# Bus_Control.net
KiCad netlist of a schematic drawn in EAGLE
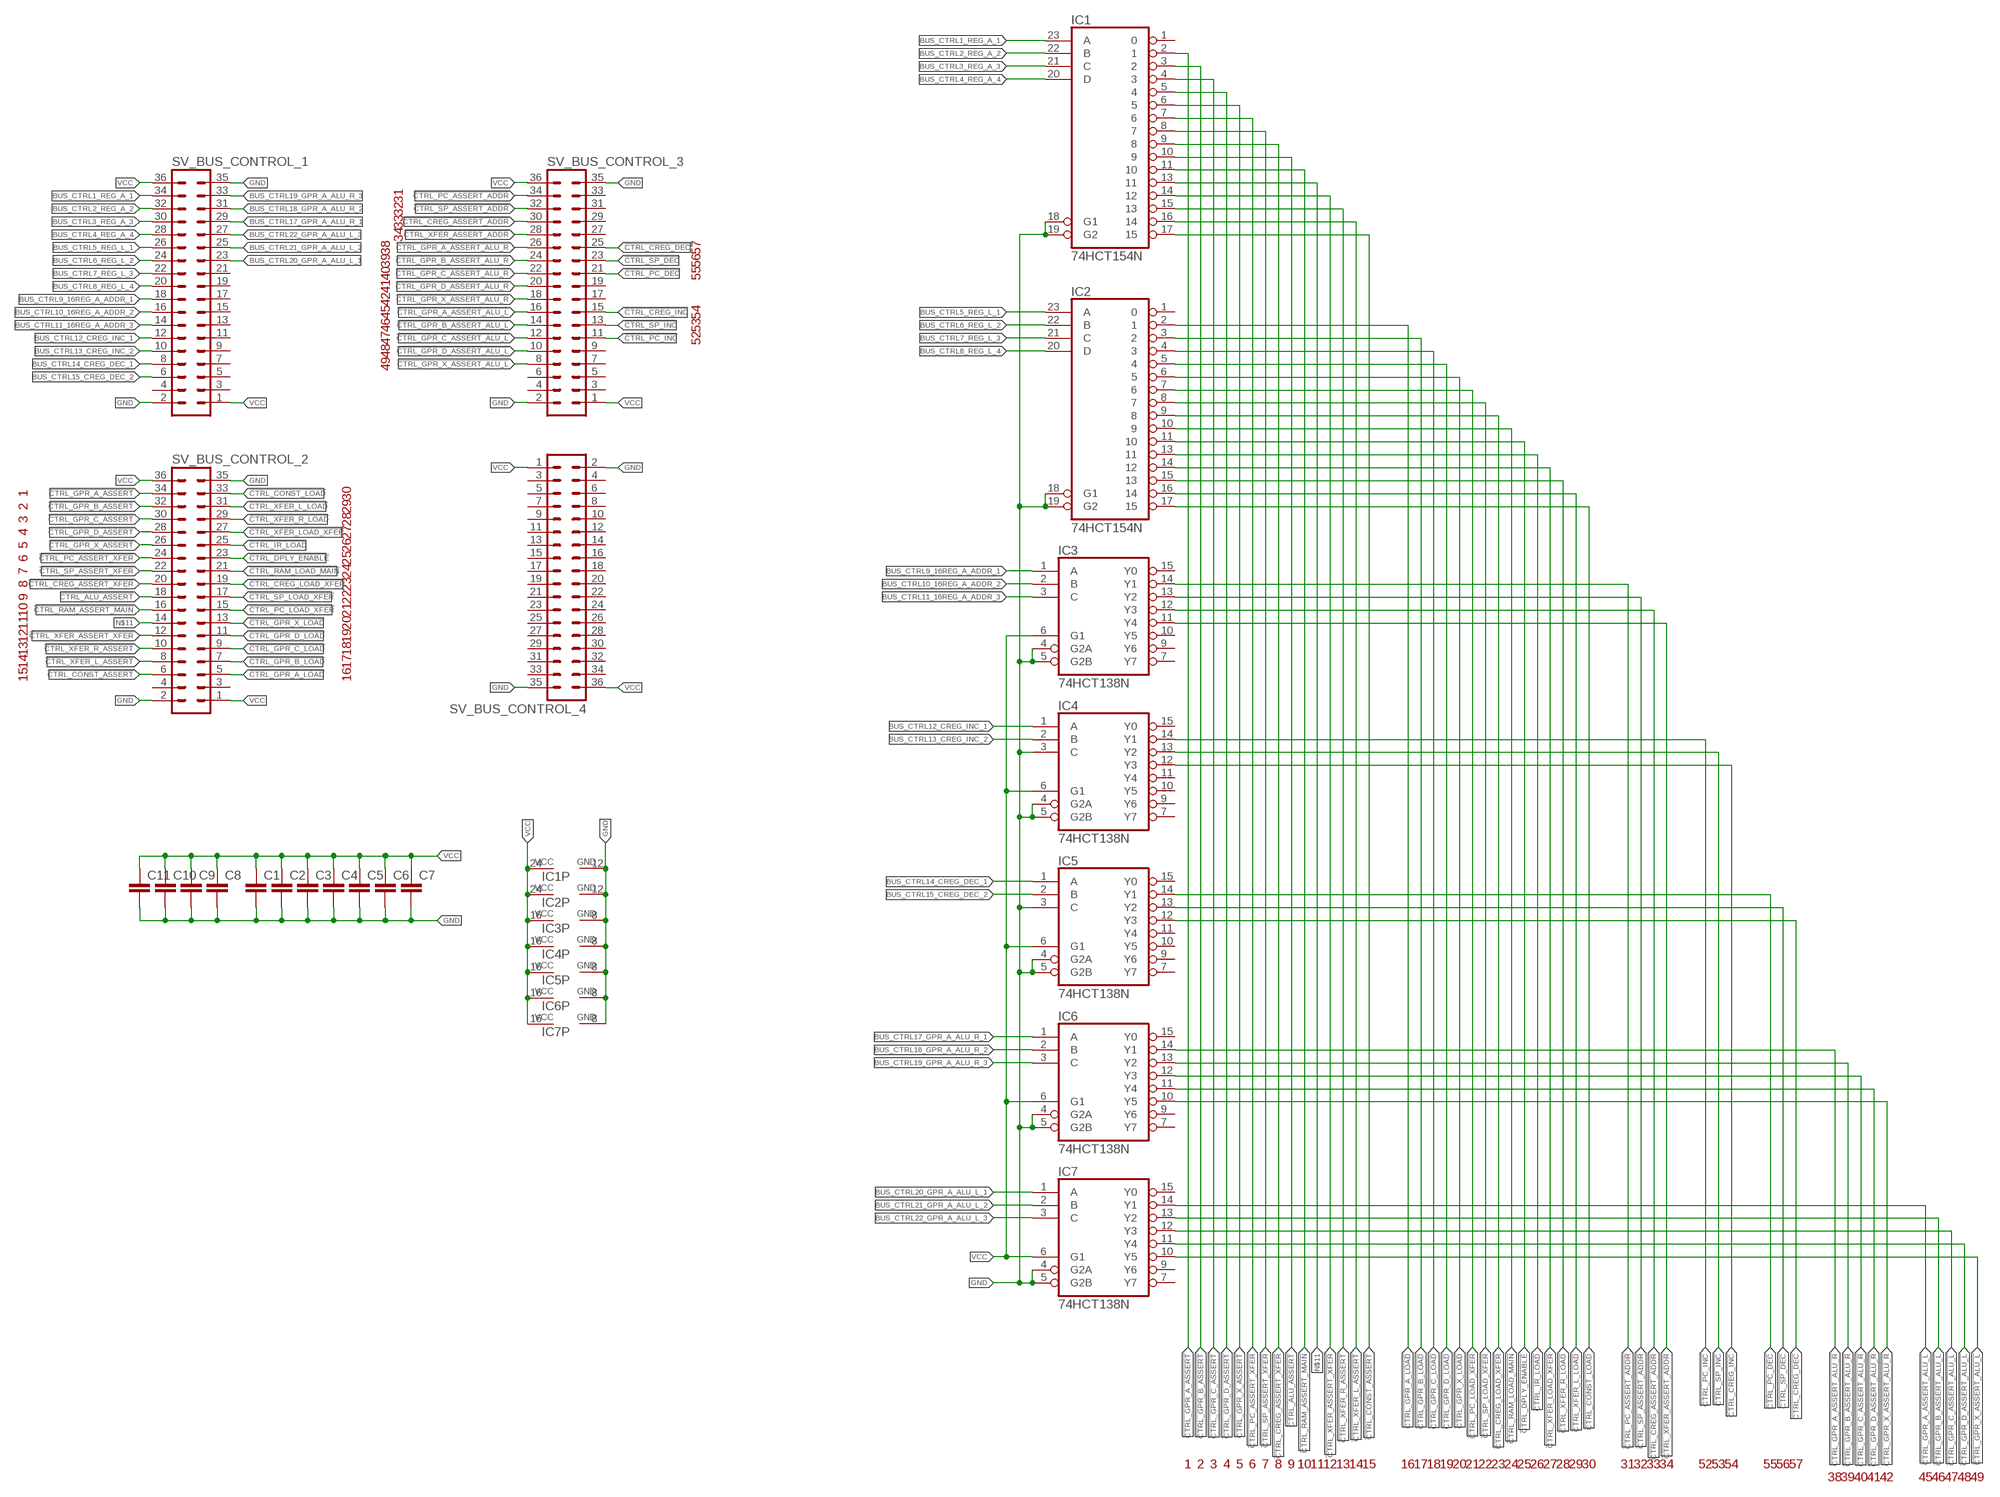
[diagram p0: schematic, sheet 1]

(export (version "E")
  (design (tool "Eeschema 10.0.6"))
  (components
    (comp (ref "C1")
      (value "C-EUC0805")
      (footprint "eagle-import:C0805")
      (libsource (lib "eagle-import") (part "C-EUC0805"))
    )
    (comp (ref "C2")
      (value "C-EUC0805")
      (footprint "eagle-import:C0805")
      (libsource (lib "eagle-import") (part "C-EUC0805"))
    )
    (comp (ref "C3")
      (value "C-EUC0805")
      (footprint "eagle-import:C0805")
      (libsource (lib "eagle-import") (part "C-EUC0805"))
    )
    (comp (ref "C4")
      (value "C-EUC0805")
      (footprint "eagle-import:C0805")
      (libsource (lib "eagle-import") (part "C-EUC0805"))
    )
    (comp (ref "C5")
      (value "C-EUC0805")
      (footprint "eagle-import:C0805")
      (libsource (lib "eagle-import") (part "C-EUC0805"))
    )
    (comp (ref "C6")
      (value "C-EUC0805")
      (footprint "eagle-import:C0805")
      (libsource (lib "eagle-import") (part "C-EUC0805"))
    )
    (comp (ref "C7")
      (value "C-EUC0805")
      (footprint "eagle-import:C0805")
      (libsource (lib "eagle-import") (part "C-EUC0805"))
    )
    (comp (ref "C8")
      (value "C-EUC0805")
      (footprint "eagle-import:C0805")
      (libsource (lib "eagle-import") (part "C-EUC0805"))
    )
    (comp (ref "C9")
      (value "C-EUC0805")
      (footprint "eagle-import:C0805")
      (libsource (lib "eagle-import") (part "C-EUC0805"))
    )
    (comp (ref "C10")
      (value "C-EUC0805")
      (footprint "eagle-import:C0805")
      (libsource (lib "eagle-import") (part "C-EUC0805"))
    )
    (comp (ref "C11")
      (value "C-EUC0805")
      (footprint "eagle-import:C0805")
      (libsource (lib "eagle-import") (part "C-EUC0805"))
    )
    (comp (ref "IC1")
      (value "74HCT154N")
      (footprint "eagle-import:DIL24-6")
      (libsource (lib "eagle-import") (part "74154NHC"))
    )
    (comp (ref "IC2")
      (value "74HCT154N")
      (footprint "eagle-import:DIL24-6")
      (libsource (lib "eagle-import") (part "74154NHC"))
    )
    (comp (ref "IC3")
      (value "74HCT138N")
      (footprint "eagle-import:DIL16")
      (libsource (lib "eagle-import") (part "74138NHCT"))
    )
    (comp (ref "IC4")
      (value "74HCT138N")
      (footprint "eagle-import:DIL16")
      (libsource (lib "eagle-import") (part "74138NHCT"))
    )
    (comp (ref "IC5")
      (value "74HCT138N")
      (footprint "eagle-import:DIL16")
      (libsource (lib "eagle-import") (part "74138NHCT"))
    )
    (comp (ref "IC6")
      (value "74HCT138N")
      (footprint "eagle-import:DIL16")
      (libsource (lib "eagle-import") (part "74138NHCT"))
    )
    (comp (ref "IC7")
      (value "74HCT138N")
      (footprint "eagle-import:DIL16")
      (libsource (lib "eagle-import") (part "74138NHCT"))
    )
    (comp (ref "SV_BUS_CONTROL_1")
      (value "MA18-2")
      (footprint "eagle-import:MA18-2")
      (libsource (lib "eagle-import") (part "MA18-2"))
    )
    (comp (ref "SV_BUS_CONTROL_2")
      (value "MA18-2")
      (footprint "eagle-import:MA18-2")
      (libsource (lib "eagle-import") (part "MA18-2"))
    )
    (comp (ref "SV_BUS_CONTROL_3")
      (value "MA18-2")
      (footprint "eagle-import:MA18-2")
      (libsource (lib "eagle-import") (part "MA18-2"))
    )
    (comp (ref "SV_BUS_CONTROL_4")
      (value "MA18-2")
      (footprint "eagle-import:MA18-2")
      (libsource (lib "eagle-import") (part "MA18-2"))
    )
  )
  (nets
    (net (code "1") (name "/~{CTRL_ALU_ASSERT}") (class "Default")
      (node (ref "IC1") (pin "10") (pinfunction "9_10") (pintype "output"))
      (node (ref "SV_BUS_CONTROL_2") (pin "18") (pinfunction "18_18") (pintype "passive"))
    )
    (net (code "2") (name "/~{CTRL_CONST_ASSERT}") (class "Default")
      (node (ref "IC1") (pin "17") (pinfunction "15_17") (pintype "output"))
      (node (ref "SV_BUS_CONTROL_2") (pin "6") (pinfunction "6_6") (pintype "passive"))
    )
    (net (code "3") (name "/~{CTRL_CONST_LOAD}") (class "Default")
      (node (ref "IC2") (pin "17") (pinfunction "15_17") (pintype "output"))
      (node (ref "SV_BUS_CONTROL_2") (pin "33") (pinfunction "33_33") (pintype "passive"))
    )
    (net (code "4") (name "/~{CTRL_CREG_ASSERT_ADDR}") (class "Default")
      (node (ref "IC3") (pin "12") (pinfunction "Y3_12") (pintype "output"))
      (node (ref "SV_BUS_CONTROL_3") (pin "30") (pinfunction "30_30") (pintype "passive"))
    )
    (net (code "5") (name "/~{CTRL_CREG_ASSERT_XFER}") (class "Default")
      (node (ref "IC1") (pin "9") (pinfunction "8_9") (pintype "output"))
      (node (ref "SV_BUS_CONTROL_2") (pin "20") (pinfunction "20_20") (pintype "passive"))
    )
    (net (code "6") (name "/~{CTRL_CREG_DEC}") (class "Default")
      (node (ref "IC5") (pin "12") (pinfunction "Y3_12") (pintype "output"))
      (node (ref "SV_BUS_CONTROL_3") (pin "25") (pinfunction "25_25") (pintype "passive"))
    )
    (net (code "7") (name "/~{CTRL_CREG_INC}") (class "Default")
      (node (ref "IC4") (pin "12") (pinfunction "Y3_12") (pintype "output"))
      (node (ref "SV_BUS_CONTROL_3") (pin "15") (pinfunction "15_15") (pintype "passive"))
    )
    (net (code "8") (name "/~{CTRL_CREG_LOAD_XFER}") (class "Default")
      (node (ref "IC2") (pin "9") (pinfunction "8_9") (pintype "output"))
      (node (ref "SV_BUS_CONTROL_2") (pin "19") (pinfunction "19_19") (pintype "passive"))
    )
    (net (code "9") (name "/~{CTRL_DPLY_ENABLE}") (class "Default")
      (node (ref "IC2") (pin "11") (pinfunction "10_11") (pintype "output"))
      (node (ref "SV_BUS_CONTROL_2") (pin "23") (pinfunction "23_23") (pintype "passive"))
    )
    (net (code "10") (name "/~{CTRL_GPR_A_ASSERT_ALU_L}") (class "Default")
      (node (ref "IC7") (pin "14") (pinfunction "Y1_14") (pintype "output"))
      (node (ref "SV_BUS_CONTROL_3") (pin "16") (pinfunction "16_16") (pintype "passive"))
    )
    (net (code "11") (name "/~{CTRL_GPR_A_ASSERT_ALU_R}") (class "Default")
      (node (ref "IC6") (pin "14") (pinfunction "Y1_14") (pintype "output"))
      (node (ref "SV_BUS_CONTROL_3") (pin "26") (pinfunction "26_26") (pintype "passive"))
    )
    (net (code "12") (name "/~{CTRL_GPR_A_ASSERT}") (class "Default")
      (node (ref "IC1") (pin "2") (pinfunction "1_2") (pintype "output"))
      (node (ref "SV_BUS_CONTROL_2") (pin "34") (pinfunction "34_34") (pintype "passive"))
    )
    (net (code "13") (name "/~{CTRL_GPR_A_LOAD}") (class "Default")
      (node (ref "IC2") (pin "2") (pinfunction "1_2") (pintype "output"))
      (node (ref "SV_BUS_CONTROL_2") (pin "5") (pinfunction "5_5") (pintype "passive"))
    )
    (net (code "14") (name "/~{CTRL_GPR_B_ASSERT_ALU_L}") (class "Default")
      (node (ref "IC7") (pin "13") (pinfunction "Y2_13") (pintype "output"))
      (node (ref "SV_BUS_CONTROL_3") (pin "14") (pinfunction "14_14") (pintype "passive"))
    )
    (net (code "15") (name "/~{CTRL_GPR_B_ASSERT_ALU_R}") (class "Default")
      (node (ref "IC6") (pin "13") (pinfunction "Y2_13") (pintype "output"))
      (node (ref "SV_BUS_CONTROL_3") (pin "24") (pinfunction "24_24") (pintype "passive"))
    )
    (net (code "16") (name "/~{CTRL_GPR_B_ASSERT}") (class "Default")
      (node (ref "IC1") (pin "3") (pinfunction "2_3") (pintype "output"))
      (node (ref "SV_BUS_CONTROL_2") (pin "32") (pinfunction "32_32") (pintype "passive"))
    )
    (net (code "17") (name "/~{CTRL_GPR_B_LOAD}") (class "Default")
      (node (ref "IC2") (pin "3") (pinfunction "2_3") (pintype "output"))
      (node (ref "SV_BUS_CONTROL_2") (pin "7") (pinfunction "7_7") (pintype "passive"))
    )
    (net (code "18") (name "/~{CTRL_GPR_C_ASSERT_ALU_L}") (class "Default")
      (node (ref "IC7") (pin "12") (pinfunction "Y3_12") (pintype "output"))
      (node (ref "SV_BUS_CONTROL_3") (pin "12") (pinfunction "12_12") (pintype "passive"))
    )
    (net (code "19") (name "/~{CTRL_GPR_C_ASSERT_ALU_R}") (class "Default")
      (node (ref "IC6") (pin "12") (pinfunction "Y3_12") (pintype "output"))
      (node (ref "SV_BUS_CONTROL_3") (pin "22") (pinfunction "22_22") (pintype "passive"))
    )
    (net (code "20") (name "/~{CTRL_GPR_C_ASSERT}") (class "Default")
      (node (ref "IC1") (pin "4") (pinfunction "3_4") (pintype "output"))
      (node (ref "SV_BUS_CONTROL_2") (pin "30") (pinfunction "30_30") (pintype "passive"))
    )
    (net (code "21") (name "/~{CTRL_GPR_C_LOAD}") (class "Default")
      (node (ref "IC2") (pin "4") (pinfunction "3_4") (pintype "output"))
      (node (ref "SV_BUS_CONTROL_2") (pin "9") (pinfunction "9_9") (pintype "passive"))
    )
    (net (code "22") (name "/~{CTRL_GPR_D_ASSERT_ALU_L}") (class "Default")
      (node (ref "IC7") (pin "11") (pinfunction "Y4_11") (pintype "output"))
      (node (ref "SV_BUS_CONTROL_3") (pin "10") (pinfunction "10_10") (pintype "passive"))
    )
    (net (code "23") (name "/~{CTRL_GPR_D_ASSERT_ALU_R}") (class "Default")
      (node (ref "IC6") (pin "11") (pinfunction "Y4_11") (pintype "output"))
      (node (ref "SV_BUS_CONTROL_3") (pin "20") (pinfunction "20_20") (pintype "passive"))
    )
    (net (code "24") (name "/~{CTRL_GPR_D_ASSERT}") (class "Default")
      (node (ref "IC1") (pin "5") (pinfunction "4_5") (pintype "output"))
      (node (ref "SV_BUS_CONTROL_2") (pin "28") (pinfunction "28_28") (pintype "passive"))
    )
    (net (code "25") (name "/~{CTRL_GPR_D_LOAD}") (class "Default")
      (node (ref "IC2") (pin "5") (pinfunction "4_5") (pintype "output"))
      (node (ref "SV_BUS_CONTROL_2") (pin "11") (pinfunction "11_11") (pintype "passive"))
    )
    (net (code "26") (name "/~{CTRL_GPR_X_ASSERT_ALU_L}") (class "Default")
      (node (ref "IC7") (pin "10") (pinfunction "Y5_10") (pintype "output"))
      (node (ref "SV_BUS_CONTROL_3") (pin "8") (pinfunction "8_8") (pintype "passive"))
    )
    (net (code "27") (name "/~{CTRL_GPR_X_ASSERT_ALU_R}") (class "Default")
      (node (ref "IC6") (pin "10") (pinfunction "Y5_10") (pintype "output"))
      (node (ref "SV_BUS_CONTROL_3") (pin "18") (pinfunction "18_18") (pintype "passive"))
    )
    (net (code "28") (name "/~{CTRL_GPR_X_ASSERT}") (class "Default")
      (node (ref "IC1") (pin "6") (pinfunction "5_6") (pintype "output"))
      (node (ref "SV_BUS_CONTROL_2") (pin "26") (pinfunction "26_26") (pintype "passive"))
    )
    (net (code "29") (name "/~{CTRL_GPR_X_LOAD}") (class "Default")
      (node (ref "IC2") (pin "6") (pinfunction "5_6") (pintype "output"))
      (node (ref "SV_BUS_CONTROL_2") (pin "13") (pinfunction "13_13") (pintype "passive"))
    )
    (net (code "30") (name "/~{CTRL_IR_LOAD}") (class "Default")
      (node (ref "IC2") (pin "13") (pinfunction "11_13") (pintype "output"))
      (node (ref "SV_BUS_CONTROL_2") (pin "25") (pinfunction "25_25") (pintype "passive"))
    )
    (net (code "31") (name "/~{CTRL_PC_ASSERT_ADDR}") (class "Default")
      (node (ref "IC3") (pin "14") (pinfunction "Y1_14") (pintype "output"))
      (node (ref "SV_BUS_CONTROL_3") (pin "34") (pinfunction "34_34") (pintype "passive"))
    )
    (net (code "32") (name "/~{CTRL_PC_ASSERT_XFER}") (class "Default")
      (node (ref "IC1") (pin "7") (pinfunction "6_7") (pintype "output"))
      (node (ref "SV_BUS_CONTROL_2") (pin "24") (pinfunction "24_24") (pintype "passive"))
    )
    (net (code "33") (name "/~{CTRL_PC_DEC}") (class "Default")
      (node (ref "IC5") (pin "14") (pinfunction "Y1_14") (pintype "output"))
      (node (ref "SV_BUS_CONTROL_3") (pin "21") (pinfunction "21_21") (pintype "passive"))
    )
    (net (code "34") (name "/~{CTRL_PC_INC}") (class "Default")
      (node (ref "IC4") (pin "14") (pinfunction "Y1_14") (pintype "output"))
      (node (ref "SV_BUS_CONTROL_3") (pin "11") (pinfunction "11_11") (pintype "passive"))
    )
    (net (code "35") (name "/~{CTRL_PC_LOAD_XFER}") (class "Default")
      (node (ref "IC2") (pin "7") (pinfunction "6_7") (pintype "output"))
      (node (ref "SV_BUS_CONTROL_2") (pin "15") (pinfunction "15_15") (pintype "passive"))
    )
    (net (code "36") (name "/~{CTRL_RAM_ASSERT_MAIN}") (class "Default")
      (node (ref "IC1") (pin "11") (pinfunction "10_11") (pintype "output"))
      (node (ref "SV_BUS_CONTROL_2") (pin "16") (pinfunction "16_16") (pintype "passive"))
    )
    (net (code "37") (name "/~{CTRL_RAM_LOAD_MAIN}") (class "Default")
      (node (ref "IC2") (pin "10") (pinfunction "9_10") (pintype "output"))
      (node (ref "SV_BUS_CONTROL_2") (pin "21") (pinfunction "21_21") (pintype "passive"))
    )
    (net (code "38") (name "/~{CTRL_SP_ASSERT_ADDR}") (class "Default")
      (node (ref "IC3") (pin "13") (pinfunction "Y2_13") (pintype "output"))
      (node (ref "SV_BUS_CONTROL_3") (pin "32") (pinfunction "32_32") (pintype "passive"))
    )
    (net (code "39") (name "/~{CTRL_SP_ASSERT_XFER}") (class "Default")
      (node (ref "IC1") (pin "8") (pinfunction "7_8") (pintype "output"))
      (node (ref "SV_BUS_CONTROL_2") (pin "22") (pinfunction "22_22") (pintype "passive"))
    )
    (net (code "40") (name "/~{CTRL_SP_DEC}") (class "Default")
      (node (ref "IC5") (pin "13") (pinfunction "Y2_13") (pintype "output"))
      (node (ref "SV_BUS_CONTROL_3") (pin "23") (pinfunction "23_23") (pintype "passive"))
    )
    (net (code "41") (name "/~{CTRL_SP_INC}") (class "Default")
      (node (ref "IC4") (pin "13") (pinfunction "Y2_13") (pintype "output"))
      (node (ref "SV_BUS_CONTROL_3") (pin "13") (pinfunction "13_13") (pintype "passive"))
    )
    (net (code "42") (name "/~{CTRL_SP_LOAD_XFER}") (class "Default")
      (node (ref "IC2") (pin "8") (pinfunction "7_8") (pintype "output"))
      (node (ref "SV_BUS_CONTROL_2") (pin "17") (pinfunction "17_17") (pintype "passive"))
    )
    (net (code "43") (name "/~{CTRL_XFER_ASSERT_ADDR}") (class "Default")
      (node (ref "IC3") (pin "11") (pinfunction "Y4_11") (pintype "output"))
      (node (ref "SV_BUS_CONTROL_3") (pin "28") (pinfunction "28_28") (pintype "passive"))
    )
    (net (code "44") (name "/~{CTRL_XFER_ASSERT_XFER}") (class "Default")
      (node (ref "IC1") (pin "14") (pinfunction "12_14") (pintype "output"))
      (node (ref "SV_BUS_CONTROL_2") (pin "12") (pinfunction "12_12") (pintype "passive"))
    )
    (net (code "45") (name "/~{CTRL_XFER_LOAD_XFER}") (class "Default")
      (node (ref "IC2") (pin "14") (pinfunction "12_14") (pintype "output"))
      (node (ref "SV_BUS_CONTROL_2") (pin "27") (pinfunction "27_27") (pintype "passive"))
    )
    (net (code "46") (name "/~{CTRL_XFER_L_ASSERT}") (class "Default")
      (node (ref "IC1") (pin "16") (pinfunction "14_16") (pintype "output"))
      (node (ref "SV_BUS_CONTROL_2") (pin "8") (pinfunction "8_8") (pintype "passive"))
    )
    (net (code "47") (name "/~{CTRL_XFER_L_LOAD}") (class "Default")
      (node (ref "IC2") (pin "16") (pinfunction "14_16") (pintype "output"))
      (node (ref "SV_BUS_CONTROL_2") (pin "31") (pinfunction "31_31") (pintype "passive"))
    )
    (net (code "48") (name "/~{CTRL_XFER_R_ASSERT}") (class "Default")
      (node (ref "IC1") (pin "15") (pinfunction "13_15") (pintype "output"))
      (node (ref "SV_BUS_CONTROL_2") (pin "10") (pinfunction "10_10") (pintype "passive"))
    )
    (net (code "49") (name "/~{CTRL_XFER_R_LOAD}") (class "Default")
      (node (ref "IC2") (pin "15") (pinfunction "13_15") (pintype "output"))
      (node (ref "SV_BUS_CONTROL_2") (pin "29") (pinfunction "29_29") (pintype "passive"))
    )
    (net (code "50") (name "BUS_CTRL1_REG_A_1") (class "Default")
      (node (ref "IC1") (pin "23") (pinfunction "A_23") (pintype "input"))
      (node (ref "SV_BUS_CONTROL_1") (pin "34") (pinfunction "34_34") (pintype "passive"))
    )
    (net (code "51") (name "BUS_CTRL2_REG_A_2") (class "Default")
      (node (ref "IC1") (pin "22") (pinfunction "B_22") (pintype "input"))
      (node (ref "SV_BUS_CONTROL_1") (pin "32") (pinfunction "32_32") (pintype "passive"))
    )
    (net (code "52") (name "BUS_CTRL3_REG_A_3") (class "Default")
      (node (ref "IC1") (pin "21") (pinfunction "C_21") (pintype "input"))
      (node (ref "SV_BUS_CONTROL_1") (pin "30") (pinfunction "30_30") (pintype "passive"))
    )
    (net (code "53") (name "BUS_CTRL4_REG_A_4") (class "Default")
      (node (ref "IC1") (pin "20") (pinfunction "D_20") (pintype "input"))
      (node (ref "SV_BUS_CONTROL_1") (pin "28") (pinfunction "28_28") (pintype "passive"))
    )
    (net (code "54") (name "BUS_CTRL5_REG_L_1") (class "Default")
      (node (ref "IC2") (pin "23") (pinfunction "A_23") (pintype "input"))
      (node (ref "SV_BUS_CONTROL_1") (pin "26") (pinfunction "26_26") (pintype "passive"))
    )
    (net (code "55") (name "BUS_CTRL6_REG_L_2") (class "Default")
      (node (ref "IC2") (pin "22") (pinfunction "B_22") (pintype "input"))
      (node (ref "SV_BUS_CONTROL_1") (pin "24") (pinfunction "24_24") (pintype "passive"))
    )
    (net (code "56") (name "BUS_CTRL7_REG_L_3") (class "Default")
      (node (ref "IC2") (pin "21") (pinfunction "C_21") (pintype "input"))
      (node (ref "SV_BUS_CONTROL_1") (pin "22") (pinfunction "22_22") (pintype "passive"))
    )
    (net (code "57") (name "BUS_CTRL8_REG_L_4") (class "Default")
      (node (ref "IC2") (pin "20") (pinfunction "D_20") (pintype "input"))
      (node (ref "SV_BUS_CONTROL_1") (pin "20") (pinfunction "20_20") (pintype "passive"))
    )
    (net (code "58") (name "BUS_CTRL9_16REG_A_ADDR_1") (class "Default")
      (node (ref "IC3") (pin "1") (pinfunction "A_1") (pintype "input"))
      (node (ref "SV_BUS_CONTROL_1") (pin "18") (pinfunction "18_18") (pintype "passive"))
    )
    (net (code "59") (name "BUS_CTRL10_16REG_A_ADDR_2") (class "Default")
      (node (ref "IC3") (pin "2") (pinfunction "B_2") (pintype "input"))
      (node (ref "SV_BUS_CONTROL_1") (pin "16") (pinfunction "16_16") (pintype "passive"))
    )
    (net (code "60") (name "BUS_CTRL11_16REG_A_ADDR_3") (class "Default")
      (node (ref "IC3") (pin "3") (pinfunction "C_3") (pintype "input"))
      (node (ref "SV_BUS_CONTROL_1") (pin "14") (pinfunction "14_14") (pintype "passive"))
    )
    (net (code "61") (name "BUS_CTRL12_CREG_INC_1") (class "Default")
      (node (ref "IC4") (pin "1") (pinfunction "A_1") (pintype "input"))
      (node (ref "SV_BUS_CONTROL_1") (pin "12") (pinfunction "12_12") (pintype "passive"))
    )
    (net (code "62") (name "BUS_CTRL13_CREG_INC_2") (class "Default")
      (node (ref "IC4") (pin "2") (pinfunction "B_2") (pintype "input"))
      (node (ref "SV_BUS_CONTROL_1") (pin "10") (pinfunction "10_10") (pintype "passive"))
    )
    (net (code "63") (name "BUS_CTRL14_CREG_DEC_1") (class "Default")
      (node (ref "IC5") (pin "1") (pinfunction "A_1") (pintype "input"))
      (node (ref "SV_BUS_CONTROL_1") (pin "8") (pinfunction "8_8") (pintype "passive"))
    )
    (net (code "64") (name "BUS_CTRL15_CREG_DEC_2") (class "Default")
      (node (ref "IC5") (pin "2") (pinfunction "B_2") (pintype "input"))
      (node (ref "SV_BUS_CONTROL_1") (pin "6") (pinfunction "6_6") (pintype "passive"))
    )
    (net (code "65") (name "BUS_CTRL17_GPR_A_ALU_R_1") (class "Default")
      (node (ref "IC6") (pin "1") (pinfunction "A_1") (pintype "input"))
      (node (ref "SV_BUS_CONTROL_1") (pin "29") (pinfunction "29_29") (pintype "passive"))
    )
    (net (code "66") (name "BUS_CTRL18_GPR_A_ALU_R_2") (class "Default")
      (node (ref "IC6") (pin "2") (pinfunction "B_2") (pintype "input"))
      (node (ref "SV_BUS_CONTROL_1") (pin "31") (pinfunction "31_31") (pintype "passive"))
    )
    (net (code "67") (name "BUS_CTRL19_GPR_A_ALU_R_3") (class "Default")
      (node (ref "IC6") (pin "3") (pinfunction "C_3") (pintype "input"))
      (node (ref "SV_BUS_CONTROL_1") (pin "33") (pinfunction "33_33") (pintype "passive"))
    )
    (net (code "68") (name "BUS_CTRL20_GPR_A_ALU_L_1") (class "Default")
      (node (ref "IC7") (pin "1") (pinfunction "A_1") (pintype "input"))
      (node (ref "SV_BUS_CONTROL_1") (pin "23") (pinfunction "23_23") (pintype "passive"))
    )
    (net (code "69") (name "BUS_CTRL21_GPR_A_ALU_L_2") (class "Default")
      (node (ref "IC7") (pin "2") (pinfunction "B_2") (pintype "input"))
      (node (ref "SV_BUS_CONTROL_1") (pin "25") (pinfunction "25_25") (pintype "passive"))
    )
    (net (code "70") (name "BUS_CTRL22_GPR_A_ALU_L_3") (class "Default")
      (node (ref "IC7") (pin "3") (pinfunction "C_3") (pintype "input"))
      (node (ref "SV_BUS_CONTROL_1") (pin "27") (pinfunction "27_27") (pintype "passive"))
    )
    (net (code "71") (name "GND") (class "Default")
      (node (ref "C1") (pin "2") (pinfunction "2_2") (pintype "passive"))
      (node (ref "C10") (pin "2") (pinfunction "2_2") (pintype "passive"))
      (node (ref "C11") (pin "2") (pinfunction "2_2") (pintype "passive"))
      (node (ref "C2") (pin "2") (pinfunction "2_2") (pintype "passive"))
      (node (ref "C3") (pin "2") (pinfunction "2_2") (pintype "passive"))
      (node (ref "C4") (pin "2") (pinfunction "2_2") (pintype "passive"))
      (node (ref "C5") (pin "2") (pinfunction "2_2") (pintype "passive"))
      (node (ref "C6") (pin "2") (pinfunction "2_2") (pintype "passive"))
      (node (ref "C7") (pin "2") (pinfunction "2_2") (pintype "passive"))
      (node (ref "C8") (pin "2") (pinfunction "2_2") (pintype "passive"))
      (node (ref "C9") (pin "2") (pinfunction "2_2") (pintype "passive"))
      (node (ref "IC1") (pin "12") (pinfunction "GND_12") (pintype "power_in"))
      (node (ref "IC1") (pin "18") (pinfunction "G1_18") (pintype "input"))
      (node (ref "IC1") (pin "19") (pinfunction "G2_19") (pintype "input"))
      (node (ref "IC2") (pin "12") (pinfunction "GND_12") (pintype "power_in"))
      (node (ref "IC2") (pin "18") (pinfunction "G1_18") (pintype "input"))
      (node (ref "IC2") (pin "19") (pinfunction "G2_19") (pintype "input"))
      (node (ref "IC3") (pin "4") (pinfunction "G2A_4") (pintype "input"))
      (node (ref "IC3") (pin "5") (pinfunction "G2B_5") (pintype "input"))
      (node (ref "IC3") (pin "8") (pinfunction "GND_8") (pintype "power_in"))
      (node (ref "IC4") (pin "3") (pinfunction "C_3") (pintype "input"))
      (node (ref "IC4") (pin "4") (pinfunction "G2A_4") (pintype "input"))
      (node (ref "IC4") (pin "5") (pinfunction "G2B_5") (pintype "input"))
      (node (ref "IC4") (pin "8") (pinfunction "GND_8") (pintype "power_in"))
      (node (ref "IC5") (pin "3") (pinfunction "C_3") (pintype "input"))
      (node (ref "IC5") (pin "4") (pinfunction "G2A_4") (pintype "input"))
      (node (ref "IC5") (pin "5") (pinfunction "G2B_5") (pintype "input"))
      (node (ref "IC5") (pin "8") (pinfunction "GND_8") (pintype "power_in"))
      (node (ref "IC6") (pin "4") (pinfunction "G2A_4") (pintype "input"))
      (node (ref "IC6") (pin "5") (pinfunction "G2B_5") (pintype "input"))
      (node (ref "IC6") (pin "8") (pinfunction "GND_8") (pintype "power_in"))
      (node (ref "IC7") (pin "4") (pinfunction "G2A_4") (pintype "input"))
      (node (ref "IC7") (pin "5") (pinfunction "G2B_5") (pintype "input"))
      (node (ref "IC7") (pin "8") (pinfunction "GND_8") (pintype "power_in"))
      (node (ref "SV_BUS_CONTROL_1") (pin "2") (pinfunction "2_2") (pintype "passive"))
      (node (ref "SV_BUS_CONTROL_1") (pin "35") (pinfunction "35_35") (pintype "passive"))
      (node (ref "SV_BUS_CONTROL_2") (pin "2") (pinfunction "2_2") (pintype "passive"))
      (node (ref "SV_BUS_CONTROL_2") (pin "35") (pinfunction "35_35") (pintype "passive"))
      (node (ref "SV_BUS_CONTROL_3") (pin "2") (pinfunction "2_2") (pintype "passive"))
      (node (ref "SV_BUS_CONTROL_3") (pin "35") (pinfunction "35_35") (pintype "passive"))
      (node (ref "SV_BUS_CONTROL_4") (pin "2") (pinfunction "2_2") (pintype "passive"))
      (node (ref "SV_BUS_CONTROL_4") (pin "35") (pinfunction "35_35") (pintype "passive"))
    )
    (net (code "72") (name "N$11") (class "Default")
      (node (ref "IC1") (pin "13") (pinfunction "11_13") (pintype "output"))
      (node (ref "SV_BUS_CONTROL_2") (pin "14") (pinfunction "14_14") (pintype "passive"))
    )
    (net (code "73") (name "VCC") (class "Default")
      (node (ref "C1") (pin "1") (pinfunction "1_1") (pintype "passive"))
      (node (ref "C10") (pin "1") (pinfunction "1_1") (pintype "passive"))
      (node (ref "C11") (pin "1") (pinfunction "1_1") (pintype "passive"))
      (node (ref "C2") (pin "1") (pinfunction "1_1") (pintype "passive"))
      (node (ref "C3") (pin "1") (pinfunction "1_1") (pintype "passive"))
      (node (ref "C4") (pin "1") (pinfunction "1_1") (pintype "passive"))
      (node (ref "C5") (pin "1") (pinfunction "1_1") (pintype "passive"))
      (node (ref "C6") (pin "1") (pinfunction "1_1") (pintype "passive"))
      (node (ref "C7") (pin "1") (pinfunction "1_1") (pintype "passive"))
      (node (ref "C8") (pin "1") (pinfunction "1_1") (pintype "passive"))
      (node (ref "C9") (pin "1") (pinfunction "1_1") (pintype "passive"))
      (node (ref "IC1") (pin "24") (pinfunction "VCC_24") (pintype "power_in"))
      (node (ref "IC2") (pin "24") (pinfunction "VCC_24") (pintype "power_in"))
      (node (ref "IC3") (pin "16") (pinfunction "VCC_16") (pintype "power_in"))
      (node (ref "IC3") (pin "6") (pinfunction "G1_6") (pintype "input"))
      (node (ref "IC4") (pin "16") (pinfunction "VCC_16") (pintype "power_in"))
      (node (ref "IC4") (pin "6") (pinfunction "G1_6") (pintype "input"))
      (node (ref "IC5") (pin "16") (pinfunction "VCC_16") (pintype "power_in"))
      (node (ref "IC5") (pin "6") (pinfunction "G1_6") (pintype "input"))
      (node (ref "IC6") (pin "16") (pinfunction "VCC_16") (pintype "power_in"))
      (node (ref "IC6") (pin "6") (pinfunction "G1_6") (pintype "input"))
      (node (ref "IC7") (pin "16") (pinfunction "VCC_16") (pintype "power_in"))
      (node (ref "IC7") (pin "6") (pinfunction "G1_6") (pintype "input"))
      (node (ref "SV_BUS_CONTROL_1") (pin "1") (pinfunction "1_1") (pintype "passive"))
      (node (ref "SV_BUS_CONTROL_1") (pin "36") (pinfunction "36_36") (pintype "passive"))
      (node (ref "SV_BUS_CONTROL_2") (pin "1") (pinfunction "1_1") (pintype "passive"))
      (node (ref "SV_BUS_CONTROL_2") (pin "36") (pinfunction "36_36") (pintype "passive"))
      (node (ref "SV_BUS_CONTROL_3") (pin "1") (pinfunction "1_1") (pintype "passive"))
      (node (ref "SV_BUS_CONTROL_3") (pin "36") (pinfunction "36_36") (pintype "passive"))
      (node (ref "SV_BUS_CONTROL_4") (pin "1") (pinfunction "1_1") (pintype "passive"))
      (node (ref "SV_BUS_CONTROL_4") (pin "36") (pinfunction "36_36") (pintype "passive"))
    )
    (net (code "74") (name "unconnected-(IC1A-0-Pad1)") (class "Default")
      (node (ref "IC1") (pin "1") (pinfunction "0_1") (pintype "output"))
    )
    (net (code "75") (name "unconnected-(IC2A-0-Pad1)") (class "Default")
      (node (ref "IC2") (pin "1") (pinfunction "0_1") (pintype "output"))
    )
    (net (code "76") (name "unconnected-(IC3A-Y0-Pad15)") (class "Default")
      (node (ref "IC3") (pin "15") (pinfunction "Y0_15") (pintype "output"))
    )
    (net (code "77") (name "unconnected-(IC3A-Y5-Pad10)") (class "Default")
      (node (ref "IC3") (pin "10") (pinfunction "Y5_10") (pintype "output"))
    )
    (net (code "78") (name "unconnected-(IC3A-Y6-Pad9)") (class "Default")
      (node (ref "IC3") (pin "9") (pinfunction "Y6_9") (pintype "output"))
    )
    (net (code "79") (name "unconnected-(IC3A-Y7-Pad7)") (class "Default")
      (node (ref "IC3") (pin "7") (pinfunction "Y7_7") (pintype "output"))
    )
    (net (code "80") (name "unconnected-(IC4A-Y0-Pad15)") (class "Default")
      (node (ref "IC4") (pin "15") (pinfunction "Y0_15") (pintype "output"))
    )
    (net (code "81") (name "unconnected-(IC4A-Y4-Pad11)") (class "Default")
      (node (ref "IC4") (pin "11") (pinfunction "Y4_11") (pintype "output"))
    )
    (net (code "82") (name "unconnected-(IC4A-Y5-Pad10)") (class "Default")
      (node (ref "IC4") (pin "10") (pinfunction "Y5_10") (pintype "output"))
    )
    (net (code "83") (name "unconnected-(IC4A-Y6-Pad9)") (class "Default")
      (node (ref "IC4") (pin "9") (pinfunction "Y6_9") (pintype "output"))
    )
    (net (code "84") (name "unconnected-(IC4A-Y7-Pad7)") (class "Default")
      (node (ref "IC4") (pin "7") (pinfunction "Y7_7") (pintype "output"))
    )
    (net (code "85") (name "unconnected-(IC5A-Y0-Pad15)") (class "Default")
      (node (ref "IC5") (pin "15") (pinfunction "Y0_15") (pintype "output"))
    )
    (net (code "86") (name "unconnected-(IC5A-Y4-Pad11)") (class "Default")
      (node (ref "IC5") (pin "11") (pinfunction "Y4_11") (pintype "output"))
    )
    (net (code "87") (name "unconnected-(IC5A-Y5-Pad10)") (class "Default")
      (node (ref "IC5") (pin "10") (pinfunction "Y5_10") (pintype "output"))
    )
    (net (code "88") (name "unconnected-(IC5A-Y6-Pad9)") (class "Default")
      (node (ref "IC5") (pin "9") (pinfunction "Y6_9") (pintype "output"))
    )
    (net (code "89") (name "unconnected-(IC5A-Y7-Pad7)") (class "Default")
      (node (ref "IC5") (pin "7") (pinfunction "Y7_7") (pintype "output"))
    )
    (net (code "90") (name "unconnected-(IC6A-Y0-Pad15)") (class "Default")
      (node (ref "IC6") (pin "15") (pinfunction "Y0_15") (pintype "output"))
    )
    (net (code "91") (name "unconnected-(IC6A-Y6-Pad9)") (class "Default")
      (node (ref "IC6") (pin "9") (pinfunction "Y6_9") (pintype "output"))
    )
    (net (code "92") (name "unconnected-(IC6A-Y7-Pad7)") (class "Default")
      (node (ref "IC6") (pin "7") (pinfunction "Y7_7") (pintype "output"))
    )
    (net (code "93") (name "unconnected-(IC7A-Y0-Pad15)") (class "Default")
      (node (ref "IC7") (pin "15") (pinfunction "Y0_15") (pintype "output"))
    )
    (net (code "94") (name "unconnected-(IC7A-Y6-Pad9)") (class "Default")
      (node (ref "IC7") (pin "9") (pinfunction "Y6_9") (pintype "output"))
    )
    (net (code "95") (name "unconnected-(IC7A-Y7-Pad7)") (class "Default")
      (node (ref "IC7") (pin "7") (pinfunction "Y7_7") (pintype "output"))
    )
    (net (code "96") (name "unconnected-(SV_BUS_CONTROL_1-Pad3)") (class "Default")
      (node (ref "SV_BUS_CONTROL_1") (pin "3") (pinfunction "3_3") (pintype "passive"))
    )
    (net (code "97") (name "unconnected-(SV_BUS_CONTROL_1-Pad4)") (class "Default")
      (node (ref "SV_BUS_CONTROL_1") (pin "4") (pinfunction "4_4") (pintype "passive"))
    )
    (net (code "98") (name "unconnected-(SV_BUS_CONTROL_1-Pad5)") (class "Default")
      (node (ref "SV_BUS_CONTROL_1") (pin "5") (pinfunction "5_5") (pintype "passive"))
    )
    (net (code "99") (name "unconnected-(SV_BUS_CONTROL_1-Pad7)") (class "Default")
      (node (ref "SV_BUS_CONTROL_1") (pin "7") (pinfunction "7_7") (pintype "passive"))
    )
    (net (code "100") (name "unconnected-(SV_BUS_CONTROL_1-Pad9)") (class "Default")
      (node (ref "SV_BUS_CONTROL_1") (pin "9") (pinfunction "9_9") (pintype "passive"))
    )
    (net (code "101") (name "unconnected-(SV_BUS_CONTROL_1-Pad11)") (class "Default")
      (node (ref "SV_BUS_CONTROL_1") (pin "11") (pinfunction "11_11") (pintype "passive"))
    )
    (net (code "102") (name "unconnected-(SV_BUS_CONTROL_1-Pad13)") (class "Default")
      (node (ref "SV_BUS_CONTROL_1") (pin "13") (pinfunction "13_13") (pintype "passive"))
    )
    (net (code "103") (name "unconnected-(SV_BUS_CONTROL_1-Pad15)") (class "Default")
      (node (ref "SV_BUS_CONTROL_1") (pin "15") (pinfunction "15_15") (pintype "passive"))
    )
    (net (code "104") (name "unconnected-(SV_BUS_CONTROL_1-Pad17)") (class "Default")
      (node (ref "SV_BUS_CONTROL_1") (pin "17") (pinfunction "17_17") (pintype "passive"))
    )
    (net (code "105") (name "unconnected-(SV_BUS_CONTROL_1-Pad19)") (class "Default")
      (node (ref "SV_BUS_CONTROL_1") (pin "19") (pinfunction "19_19") (pintype "passive"))
    )
    (net (code "106") (name "unconnected-(SV_BUS_CONTROL_1-Pad21)") (class "Default")
      (node (ref "SV_BUS_CONTROL_1") (pin "21") (pinfunction "21_21") (pintype "passive"))
    )
    (net (code "107") (name "unconnected-(SV_BUS_CONTROL_2-Pad3)") (class "Default")
      (node (ref "SV_BUS_CONTROL_2") (pin "3") (pinfunction "3_3") (pintype "passive"))
    )
    (net (code "108") (name "unconnected-(SV_BUS_CONTROL_2-Pad4)") (class "Default")
      (node (ref "SV_BUS_CONTROL_2") (pin "4") (pinfunction "4_4") (pintype "passive"))
    )
    (net (code "109") (name "unconnected-(SV_BUS_CONTROL_3-Pad3)") (class "Default")
      (node (ref "SV_BUS_CONTROL_3") (pin "3") (pinfunction "3_3") (pintype "passive"))
    )
    (net (code "110") (name "unconnected-(SV_BUS_CONTROL_3-Pad4)") (class "Default")
      (node (ref "SV_BUS_CONTROL_3") (pin "4") (pinfunction "4_4") (pintype "passive"))
    )
    (net (code "111") (name "unconnected-(SV_BUS_CONTROL_3-Pad5)") (class "Default")
      (node (ref "SV_BUS_CONTROL_3") (pin "5") (pinfunction "5_5") (pintype "passive"))
    )
    (net (code "112") (name "unconnected-(SV_BUS_CONTROL_3-Pad6)") (class "Default")
      (node (ref "SV_BUS_CONTROL_3") (pin "6") (pinfunction "6_6") (pintype "passive"))
    )
    (net (code "113") (name "unconnected-(SV_BUS_CONTROL_3-Pad7)") (class "Default")
      (node (ref "SV_BUS_CONTROL_3") (pin "7") (pinfunction "7_7") (pintype "passive"))
    )
    (net (code "114") (name "unconnected-(SV_BUS_CONTROL_3-Pad9)") (class "Default")
      (node (ref "SV_BUS_CONTROL_3") (pin "9") (pinfunction "9_9") (pintype "passive"))
    )
    (net (code "115") (name "unconnected-(SV_BUS_CONTROL_3-Pad17)") (class "Default")
      (node (ref "SV_BUS_CONTROL_3") (pin "17") (pinfunction "17_17") (pintype "passive"))
    )
    (net (code "116") (name "unconnected-(SV_BUS_CONTROL_3-Pad19)") (class "Default")
      (node (ref "SV_BUS_CONTROL_3") (pin "19") (pinfunction "19_19") (pintype "passive"))
    )
    (net (code "117") (name "unconnected-(SV_BUS_CONTROL_3-Pad27)") (class "Default")
      (node (ref "SV_BUS_CONTROL_3") (pin "27") (pinfunction "27_27") (pintype "passive"))
    )
    (net (code "118") (name "unconnected-(SV_BUS_CONTROL_3-Pad29)") (class "Default")
      (node (ref "SV_BUS_CONTROL_3") (pin "29") (pinfunction "29_29") (pintype "passive"))
    )
    (net (code "119") (name "unconnected-(SV_BUS_CONTROL_3-Pad31)") (class "Default")
      (node (ref "SV_BUS_CONTROL_3") (pin "31") (pinfunction "31_31") (pintype "passive"))
    )
    (net (code "120") (name "unconnected-(SV_BUS_CONTROL_3-Pad33)") (class "Default")
      (node (ref "SV_BUS_CONTROL_3") (pin "33") (pinfunction "33_33") (pintype "passive"))
    )
    (net (code "121") (name "unconnected-(SV_BUS_CONTROL_4-Pad3)") (class "Default")
      (node (ref "SV_BUS_CONTROL_4") (pin "3") (pinfunction "3_3") (pintype "passive"))
    )
    (net (code "122") (name "unconnected-(SV_BUS_CONTROL_4-Pad4)") (class "Default")
      (node (ref "SV_BUS_CONTROL_4") (pin "4") (pinfunction "4_4") (pintype "passive"))
    )
    (net (code "123") (name "unconnected-(SV_BUS_CONTROL_4-Pad5)") (class "Default")
      (node (ref "SV_BUS_CONTROL_4") (pin "5") (pinfunction "5_5") (pintype "passive"))
    )
    (net (code "124") (name "unconnected-(SV_BUS_CONTROL_4-Pad6)") (class "Default")
      (node (ref "SV_BUS_CONTROL_4") (pin "6") (pinfunction "6_6") (pintype "passive"))
    )
    (net (code "125") (name "unconnected-(SV_BUS_CONTROL_4-Pad7)") (class "Default")
      (node (ref "SV_BUS_CONTROL_4") (pin "7") (pinfunction "7_7") (pintype "passive"))
    )
    (net (code "126") (name "unconnected-(SV_BUS_CONTROL_4-Pad8)") (class "Default")
      (node (ref "SV_BUS_CONTROL_4") (pin "8") (pinfunction "8_8") (pintype "passive"))
    )
    (net (code "127") (name "unconnected-(SV_BUS_CONTROL_4-Pad9)") (class "Default")
      (node (ref "SV_BUS_CONTROL_4") (pin "9") (pinfunction "9_9") (pintype "passive"))
    )
    (net (code "128") (name "unconnected-(SV_BUS_CONTROL_4-Pad10)") (class "Default")
      (node (ref "SV_BUS_CONTROL_4") (pin "10") (pinfunction "10_10") (pintype "passive"))
    )
    (net (code "129") (name "unconnected-(SV_BUS_CONTROL_4-Pad11)") (class "Default")
      (node (ref "SV_BUS_CONTROL_4") (pin "11") (pinfunction "11_11") (pintype "passive"))
    )
    (net (code "130") (name "unconnected-(SV_BUS_CONTROL_4-Pad12)") (class "Default")
      (node (ref "SV_BUS_CONTROL_4") (pin "12") (pinfunction "12_12") (pintype "passive"))
    )
    (net (code "131") (name "unconnected-(SV_BUS_CONTROL_4-Pad13)") (class "Default")
      (node (ref "SV_BUS_CONTROL_4") (pin "13") (pinfunction "13_13") (pintype "passive"))
    )
    (net (code "132") (name "unconnected-(SV_BUS_CONTROL_4-Pad14)") (class "Default")
      (node (ref "SV_BUS_CONTROL_4") (pin "14") (pinfunction "14_14") (pintype "passive"))
    )
    (net (code "133") (name "unconnected-(SV_BUS_CONTROL_4-Pad15)") (class "Default")
      (node (ref "SV_BUS_CONTROL_4") (pin "15") (pinfunction "15_15") (pintype "passive"))
    )
    (net (code "134") (name "unconnected-(SV_BUS_CONTROL_4-Pad16)") (class "Default")
      (node (ref "SV_BUS_CONTROL_4") (pin "16") (pinfunction "16_16") (pintype "passive"))
    )
    (net (code "135") (name "unconnected-(SV_BUS_CONTROL_4-Pad17)") (class "Default")
      (node (ref "SV_BUS_CONTROL_4") (pin "17") (pinfunction "17_17") (pintype "passive"))
    )
    (net (code "136") (name "unconnected-(SV_BUS_CONTROL_4-Pad18)") (class "Default")
      (node (ref "SV_BUS_CONTROL_4") (pin "18") (pinfunction "18_18") (pintype "passive"))
    )
    (net (code "137") (name "unconnected-(SV_BUS_CONTROL_4-Pad19)") (class "Default")
      (node (ref "SV_BUS_CONTROL_4") (pin "19") (pinfunction "19_19") (pintype "passive"))
    )
    (net (code "138") (name "unconnected-(SV_BUS_CONTROL_4-Pad20)") (class "Default")
      (node (ref "SV_BUS_CONTROL_4") (pin "20") (pinfunction "20_20") (pintype "passive"))
    )
    (net (code "139") (name "unconnected-(SV_BUS_CONTROL_4-Pad21)") (class "Default")
      (node (ref "SV_BUS_CONTROL_4") (pin "21") (pinfunction "21_21") (pintype "passive"))
    )
    (net (code "140") (name "unconnected-(SV_BUS_CONTROL_4-Pad22)") (class "Default")
      (node (ref "SV_BUS_CONTROL_4") (pin "22") (pinfunction "22_22") (pintype "passive"))
    )
    (net (code "141") (name "unconnected-(SV_BUS_CONTROL_4-Pad23)") (class "Default")
      (node (ref "SV_BUS_CONTROL_4") (pin "23") (pinfunction "23_23") (pintype "passive"))
    )
    (net (code "142") (name "unconnected-(SV_BUS_CONTROL_4-Pad24)") (class "Default")
      (node (ref "SV_BUS_CONTROL_4") (pin "24") (pinfunction "24_24") (pintype "passive"))
    )
    (net (code "143") (name "unconnected-(SV_BUS_CONTROL_4-Pad25)") (class "Default")
      (node (ref "SV_BUS_CONTROL_4") (pin "25") (pinfunction "25_25") (pintype "passive"))
    )
    (net (code "144") (name "unconnected-(SV_BUS_CONTROL_4-Pad26)") (class "Default")
      (node (ref "SV_BUS_CONTROL_4") (pin "26") (pinfunction "26_26") (pintype "passive"))
    )
    (net (code "145") (name "unconnected-(SV_BUS_CONTROL_4-Pad27)") (class "Default")
      (node (ref "SV_BUS_CONTROL_4") (pin "27") (pinfunction "27_27") (pintype "passive"))
    )
    (net (code "146") (name "unconnected-(SV_BUS_CONTROL_4-Pad28)") (class "Default")
      (node (ref "SV_BUS_CONTROL_4") (pin "28") (pinfunction "28_28") (pintype "passive"))
    )
    (net (code "147") (name "unconnected-(SV_BUS_CONTROL_4-Pad29)") (class "Default")
      (node (ref "SV_BUS_CONTROL_4") (pin "29") (pinfunction "29_29") (pintype "passive"))
    )
    (net (code "148") (name "unconnected-(SV_BUS_CONTROL_4-Pad30)") (class "Default")
      (node (ref "SV_BUS_CONTROL_4") (pin "30") (pinfunction "30_30") (pintype "passive"))
    )
    (net (code "149") (name "unconnected-(SV_BUS_CONTROL_4-Pad31)") (class "Default")
      (node (ref "SV_BUS_CONTROL_4") (pin "31") (pinfunction "31_31") (pintype "passive"))
    )
    (net (code "150") (name "unconnected-(SV_BUS_CONTROL_4-Pad32)") (class "Default")
      (node (ref "SV_BUS_CONTROL_4") (pin "32") (pinfunction "32_32") (pintype "passive"))
    )
    (net (code "151") (name "unconnected-(SV_BUS_CONTROL_4-Pad33)") (class "Default")
      (node (ref "SV_BUS_CONTROL_4") (pin "33") (pinfunction "33_33") (pintype "passive"))
    )
    (net (code "152") (name "unconnected-(SV_BUS_CONTROL_4-Pad34)") (class "Default")
      (node (ref "SV_BUS_CONTROL_4") (pin "34") (pinfunction "34_34") (pintype "passive"))
    )
  )
)
